# MainBoard_HMI.net
KiCad netlist of a schematic drawn in Altium Designer
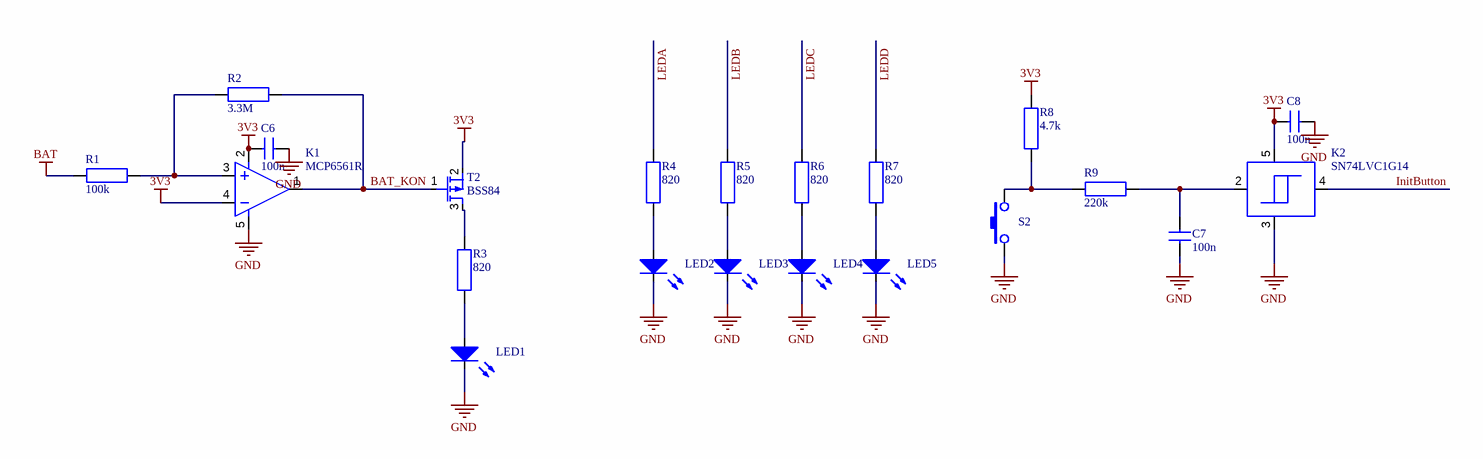
[diagram p0: MainBoard_HMI.SchDoc]

(export (version "E")
  (design (tool "Eeschema 10.0.6"))
  (components
    (comp (ref "C6")
      (value "100n")
      (footprint "0805_C")
      (description "Normaler Kondensator")
      (libsource (lib "MainBoard") (part "C?"))
    )
    (comp (ref "C7")
      (value "100n")
      (footprint "0805_C")
      (description "Normaler Kondensator")
      (libsource (lib "MainBoard") (part "C?"))
    )
    (comp (ref "C8")
      (value "100n")
      (footprint "0805_C")
      (description "Normaler Kondensator")
      (libsource (lib "MainBoard") (part "C?"))
    )
    (comp (ref "K1") (value "MCP6561R") (footprint "SOT23-5") (libsource (lib "MainBoard") (part "OPAMP")))
    (comp (ref "K2")
      (value "SN74LVC1G14")
      (footprint "SOT23-5")
      (libsource (lib "MainBoard") (part "schmitt"))
    )
    (comp (ref "LED1")
      (value "~")
      (footprint "LED_THT_3mm_RM_2.54mm")
      (libsource (lib "Sch_Lib") (part "LED"))
    )
    (comp (ref "LED2")
      (value "~")
      (footprint "LED_THT_3mm_RM_2.54mm")
      (libsource (lib "Sch_Lib") (part "LED"))
    )
    (comp (ref "LED3")
      (value "~")
      (footprint "LED_THT_3mm_RM_2.54mm")
      (libsource (lib "Sch_Lib") (part "LED"))
    )
    (comp (ref "LED4")
      (value "~")
      (footprint "LED_THT_3mm_RM_2.54mm")
      (libsource (lib "Sch_Lib") (part "LED"))
    )
    (comp (ref "LED5")
      (value "~")
      (footprint "LED_THT_3mm_RM_2.54mm")
      (libsource (lib "Sch_Lib") (part "LED"))
    )
    (comp (ref "R1")
      (value "100k")
      (footprint "0805_R")
      (description "Normaler Widerstand")
      (libsource (lib "MainBoard") (part "R?"))
    )
    (comp (ref "R2")
      (value "3.3M")
      (footprint "0805_R")
      (description "Normaler Widerstand")
      (libsource (lib "MainBoard") (part "R?"))
    )
    (comp (ref "R3")
      (value "820")
      (footprint "0805_R")
      (description "Normaler Widerstand")
      (libsource (lib "MainBoard") (part "R?"))
    )
    (comp (ref "R4")
      (value "820")
      (footprint "0805_R")
      (description "Normaler Widerstand")
      (libsource (lib "MainBoard") (part "R?"))
    )
    (comp (ref "R5")
      (value "820")
      (footprint "0805_R")
      (description "Normaler Widerstand")
      (libsource (lib "MainBoard") (part "R?"))
    )
    (comp (ref "R6")
      (value "820")
      (footprint "0805_R")
      (description "Normaler Widerstand")
      (libsource (lib "MainBoard") (part "R?"))
    )
    (comp (ref "R7")
      (value "820")
      (footprint "0805_R")
      (description "Normaler Widerstand")
      (libsource (lib "MainBoard") (part "R?"))
    )
    (comp (ref "R8")
      (value "4.7k")
      (footprint "0805_R")
      (description "Normaler Widerstand")
      (libsource (lib "MainBoard") (part "R?"))
    )
    (comp (ref "R9")
      (value "220k")
      (footprint "0805_r")
      (description "Normaler Widerstand")
      (libsource (lib "MainBoard") (part "R?"))
    )
    (comp (ref "S2") (value "S2") (footprint "SIP2") (libsource (lib "DEVICE_HSLU") (part "SW-PB")))
    (comp (ref "T2")
      (value "BSS84")
      (footprint "SOT23-3")
      (description "MOSFET-P 1D,2G,3S")
      (libsource (lib "Sch_Lib") (part "MOSFET-P 1D,2G,3S"))
    )
  )
  (nets
    (net (code "1") (name "/BAT_KON") (class "Default")
      (node (ref "K1") (pin "1") (pinfunction "1_1") (pintype "passive"))
      (node (ref "R2") (pin "1") (pintype "passive"))
      (node (ref "T2") (pin "1") (pinfunction "G_1") (pintype "passive"))
    )
    (net (code "2") (name "/InitButton") (class "Default")
      (node (ref "K2") (pin "4") (pinfunction "4_4") (pintype "passive"))
    )
    (net (code "3") (name "/LEDA") (class "Default") (node (ref "R4") (pin "1") (pintype "passive")))
    (net (code "4") (name "/LEDB") (class "Default") (node (ref "R5") (pin "1") (pintype "passive")))
    (net (code "5") (name "/LEDC") (class "Default") (node (ref "R6") (pin "1") (pintype "passive")))
    (net (code "6") (name "/LEDD") (class "Default") (node (ref "R7") (pin "1") (pintype "passive")))
    (net (code "7") (name "3V3") (class "Default")
      (node (ref "C6") (pin "1") (pinfunction "1_1") (pintype "passive"))
      (node (ref "C8") (pin "1") (pinfunction "1_1") (pintype "passive"))
      (node (ref "K1") (pin "2") (pinfunction "2_2") (pintype "passive"))
      (node (ref "K1") (pin "4") (pinfunction "4_4") (pintype "passive"))
      (node (ref "K2") (pin "5") (pinfunction "5_5") (pintype "passive"))
      (node (ref "R8") (pin "1") (pintype "passive"))
      (node (ref "T2") (pin "2") (pinfunction "S_2") (pintype "passive"))
    )
    (net (code "8") (name "BAT") (class "Default") (node (ref "R1") (pin "2") (pintype "passive")))
    (net (code "9") (name "GND") (class "Default")
      (node (ref "C6") (pin "2") (pinfunction "2_2") (pintype "passive"))
      (node (ref "C7") (pin "1") (pinfunction "1_1") (pintype "passive"))
      (node (ref "C8") (pin "2") (pinfunction "2_2") (pintype "passive"))
      (node (ref "K1") (pin "5") (pinfunction "5_5") (pintype "passive"))
      (node (ref "K2") (pin "3") (pinfunction "3_3") (pintype "passive"))
      (node (ref "LED1") (pin "2") (pinfunction "K_2") (pintype "passive"))
      (node (ref "LED2") (pin "2") (pinfunction "K_2") (pintype "passive"))
      (node (ref "LED3") (pin "2") (pinfunction "K_2") (pintype "passive"))
      (node (ref "LED4") (pin "2") (pinfunction "K_2") (pintype "passive"))
      (node (ref "LED5") (pin "2") (pinfunction "K_2") (pintype "passive"))
      (node (ref "S2") (pin "1") (pintype "passive"))
    )
    (net (code "10") (name "Net-(C7-Pad2)") (class "Default")
      (node (ref "C7") (pin "2") (pinfunction "2_2") (pintype "passive"))
      (node (ref "K2") (pin "2") (pinfunction "2_2") (pintype "passive"))
      (node (ref "R9") (pin "2") (pintype "passive"))
    )
    (net (code "11") (name "Net-(K1-Pad3)") (class "Default")
      (node (ref "K1") (pin "3") (pinfunction "3_3") (pintype "passive"))
      (node (ref "R1") (pin "1") (pintype "passive"))
      (node (ref "R2") (pin "2") (pintype "passive"))
    )
    (net (code "12") (name "Net-(LED1-A)") (class "Default")
      (node (ref "LED1") (pin "1") (pinfunction "A_1") (pintype "passive"))
      (node (ref "R3") (pin "2") (pintype "passive"))
    )
    (net (code "13") (name "Net-(LED2-A)") (class "Default")
      (node (ref "LED2") (pin "1") (pinfunction "A_1") (pintype "passive"))
      (node (ref "R4") (pin "2") (pintype "passive"))
    )
    (net (code "14") (name "Net-(LED3-A)") (class "Default")
      (node (ref "LED3") (pin "1") (pinfunction "A_1") (pintype "passive"))
      (node (ref "R5") (pin "2") (pintype "passive"))
    )
    (net (code "15") (name "Net-(LED4-A)") (class "Default")
      (node (ref "LED4") (pin "1") (pinfunction "A_1") (pintype "passive"))
      (node (ref "R6") (pin "2") (pintype "passive"))
    )
    (net (code "16") (name "Net-(LED5-A)") (class "Default")
      (node (ref "LED5") (pin "1") (pinfunction "A_1") (pintype "passive"))
      (node (ref "R7") (pin "2") (pintype "passive"))
    )
    (net (code "17") (name "Net-(R8-Pad2)") (class "Default")
      (node (ref "R8") (pin "2") (pintype "passive"))
      (node (ref "R9") (pin "1") (pintype "passive"))
      (node (ref "S2") (pin "2") (pintype "passive"))
    )
    (net (code "18") (name "Net-(T2-D)") (class "Default")
      (node (ref "R3") (pin "1") (pintype "passive"))
      (node (ref "T2") (pin "3") (pinfunction "D_3") (pintype "passive"))
    )
  )
)
